# M708B.net
KiCad netlist of a schematic drawn in EAGLE
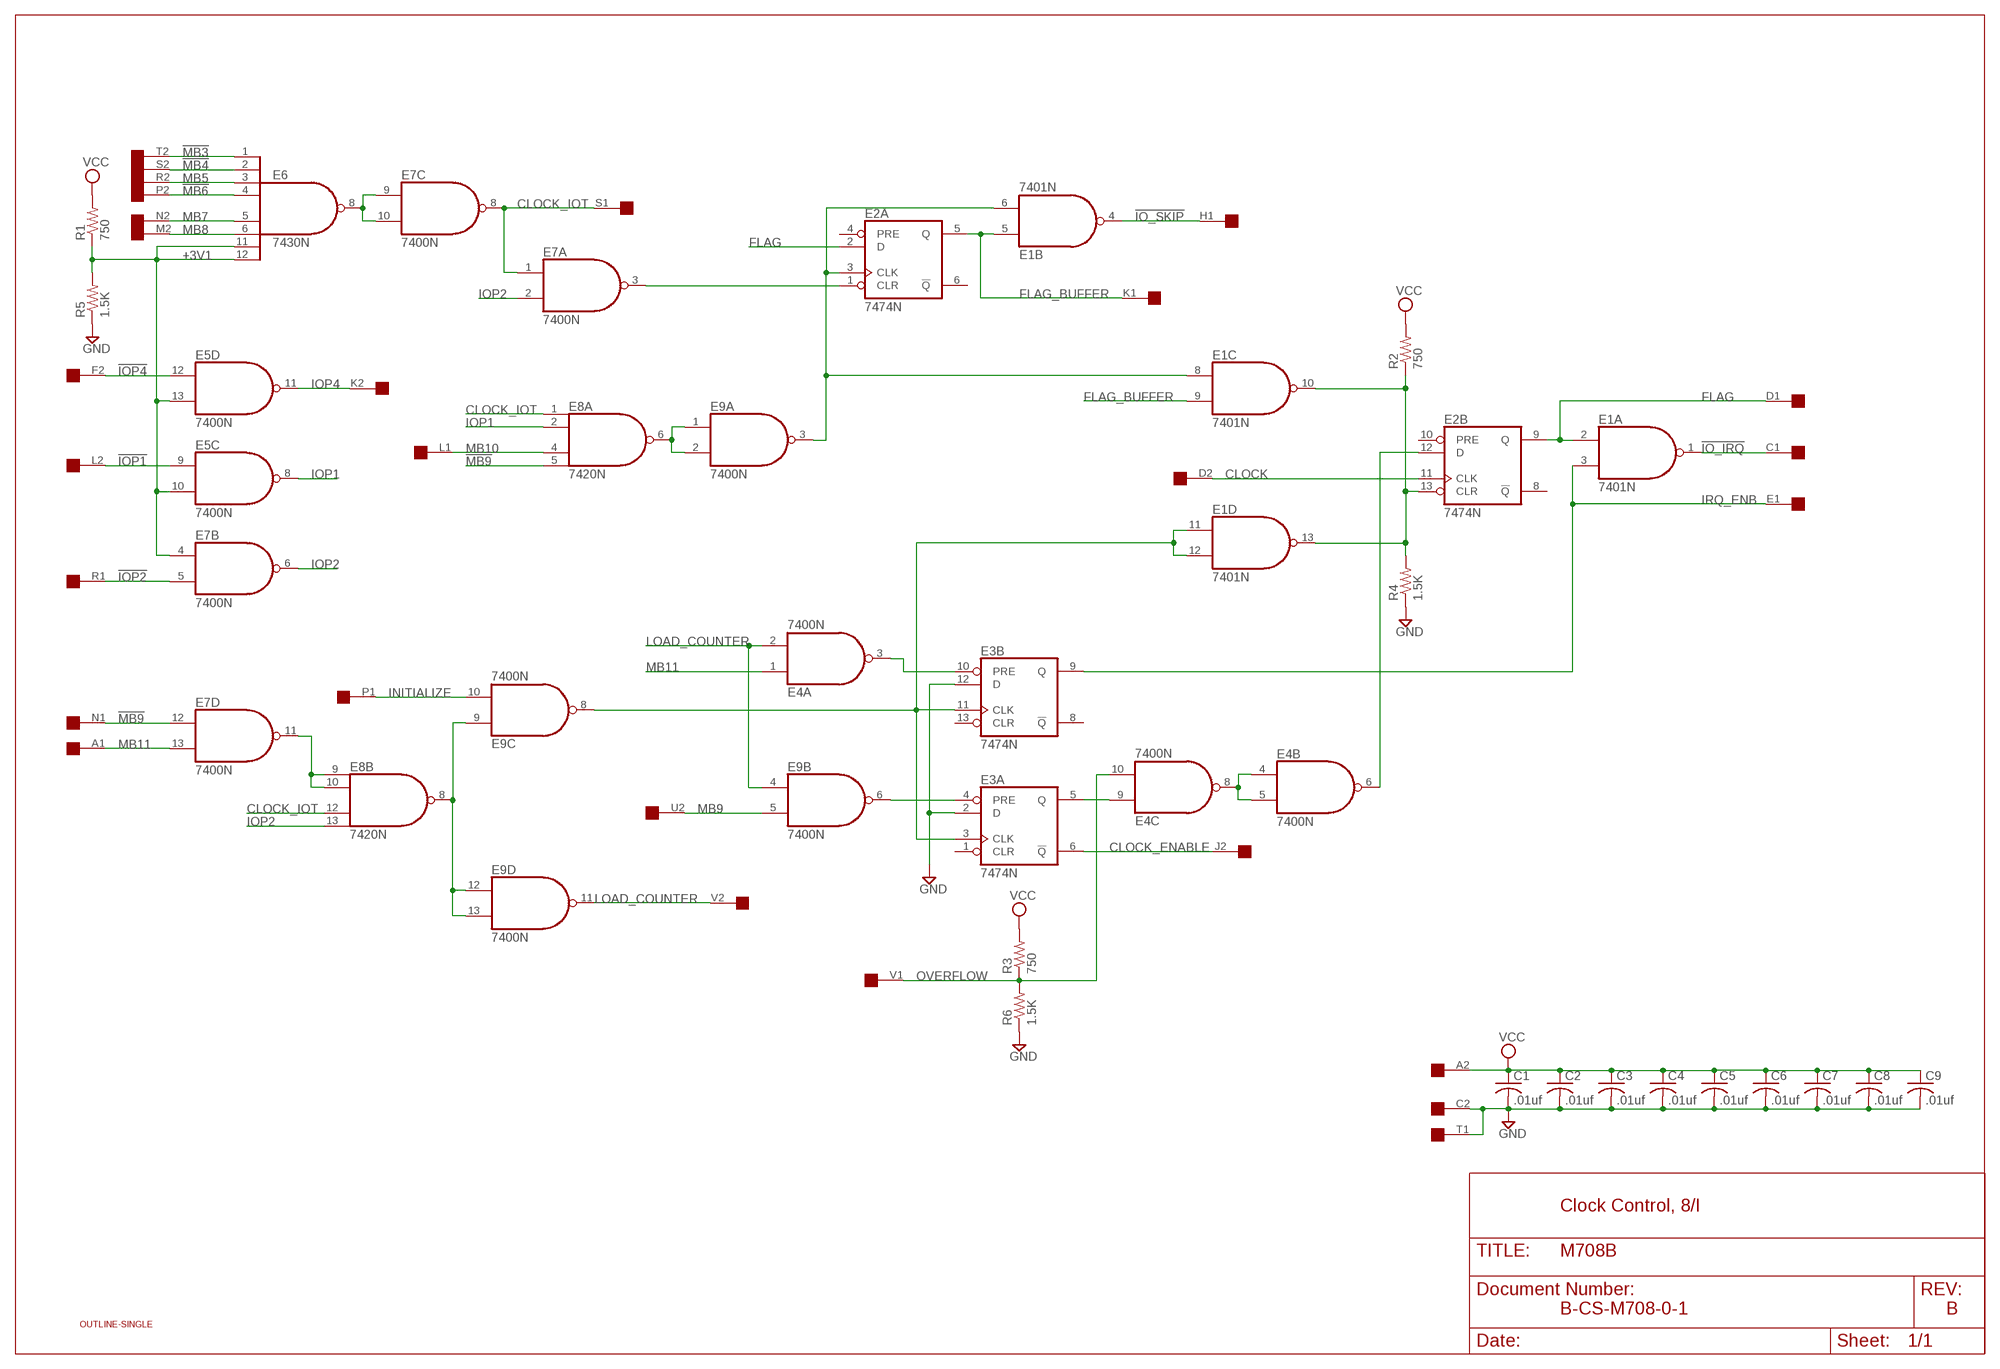
[diagram p0: schematic, sheet 1]

(export (version "E")
  (design (tool "Eeschema 10.0.6"))
  (components
    (comp (ref "C1")
      (value ".01uf")
      (footprint "eagle-import:C075-032X103")
      (libsource (lib "eagle-import") (part "C-US075-032X103"))
    )
    (comp (ref "C2")
      (value ".01uf")
      (footprint "eagle-import:C075-032X103")
      (libsource (lib "eagle-import") (part "C-US075-032X103"))
    )
    (comp (ref "C3")
      (value ".01uf")
      (footprint "eagle-import:C075-032X103")
      (libsource (lib "eagle-import") (part "C-US075-032X103"))
    )
    (comp (ref "C4")
      (value ".01uf")
      (footprint "eagle-import:C075-032X103")
      (libsource (lib "eagle-import") (part "C-US075-032X103"))
    )
    (comp (ref "C5")
      (value ".01uf")
      (footprint "eagle-import:C075-032X103")
      (libsource (lib "eagle-import") (part "C-US075-032X103"))
    )
    (comp (ref "C6")
      (value ".01uf")
      (footprint "eagle-import:C075-032X103")
      (libsource (lib "eagle-import") (part "C-US075-032X103"))
    )
    (comp (ref "C7")
      (value ".01uf")
      (footprint "eagle-import:C075-032X103")
      (libsource (lib "eagle-import") (part "C-US075-032X103"))
    )
    (comp (ref "C8")
      (value ".01uf")
      (footprint "eagle-import:C075-032X103")
      (libsource (lib "eagle-import") (part "C-US075-032X103"))
    )
    (comp (ref "C9")
      (value ".01uf")
      (footprint "eagle-import:C075-032X103")
      (libsource (lib "eagle-import") (part "C-US075-032X103"))
    )
    (comp (ref "E1")
      (value "7401N")
      (footprint "eagle-import:DIL14")
      (libsource (lib "eagle-import") (part "7401NLS"))
    )
    (comp (ref "E2")
      (value "7474N")
      (footprint "eagle-import:DIL14")
      (libsource (lib "eagle-import") (part "7474NS"))
    )
    (comp (ref "E3")
      (value "7474N")
      (footprint "eagle-import:DIL14")
      (libsource (lib "eagle-import") (part "7474NS"))
    )
    (comp (ref "E4")
      (value "7400N")
      (footprint "eagle-import:DIL14")
      (libsource (lib "eagle-import") (part "7400N"))
    )
    (comp (ref "E5")
      (value "7400N")
      (footprint "eagle-import:DIL14")
      (libsource (lib "eagle-import") (part "7400N"))
    )
    (comp (ref "E6")
      (value "7430N")
      (footprint "eagle-import:DIL14")
      (libsource (lib "eagle-import") (part "7430N"))
    )
    (comp (ref "E7")
      (value "7400N")
      (footprint "eagle-import:DIL14")
      (libsource (lib "eagle-import") (part "7400N"))
    )
    (comp (ref "E8")
      (value "7420N")
      (footprint "eagle-import:DIL14")
      (libsource (lib "eagle-import") (part "7420NS"))
    )
    (comp (ref "E9")
      (value "7400N")
      (footprint "eagle-import:DIL14")
      (libsource (lib "eagle-import") (part "7400N"))
    )
    (comp (ref "R1")
      (value "750")
      (footprint "eagle-import:0207_10")
      (libsource (lib "eagle-import") (part "R-US_0207/10"))
    )
    (comp (ref "R2")
      (value "750")
      (footprint "eagle-import:0207_10")
      (libsource (lib "eagle-import") (part "R-US_0207/10"))
    )
    (comp (ref "R3")
      (value "750")
      (footprint "eagle-import:0207_10")
      (libsource (lib "eagle-import") (part "R-US_0207/10"))
    )
    (comp (ref "R4")
      (value "1.5K")
      (footprint "eagle-import:0207_10")
      (libsource (lib "eagle-import") (part "R-US_0207/10"))
    )
    (comp (ref "R5")
      (value "1.5K")
      (footprint "eagle-import:0207_10")
      (libsource (lib "eagle-import") (part "R-US_0207/10"))
    )
    (comp (ref "R6")
      (value "1.5K")
      (footprint "eagle-import:0207_10")
      (libsource (lib "eagle-import") (part "R-US_0207/10"))
    )
    (comp (ref "U$1")
      (value "SINGLE")
      (footprint "eagle-import:EDGE-CON2")
      (libsource (lib "eagle-import") (part "SINGLE"))
    )
    (comp (ref "U$4")
      (value "OUTLINE-SINGLE")
      (footprint "eagle-import:SINGLE")
      (libsource (lib "eagle-import") (part "OUTLINE-SINGLE"))
    )
  )
  (nets
    (net (code "1") (name "/+3V1") (class "Default")
      (node (ref "E5") (pin "10") (pinfunction "I1_10") (pintype "input"))
      (node (ref "E5") (pin "13") (pinfunction "I1_13") (pintype "input"))
      (node (ref "E6") (pin "11") (pinfunction "I6_11") (pintype "input"))
      (node (ref "E6") (pin "12") (pinfunction "I7_12") (pintype "input"))
      (node (ref "E7") (pin "4") (pinfunction "I0_4") (pintype "input"))
      (node (ref "R1") (pin "1") (pinfunction "1_1") (pintype "passive"))
      (node (ref "R5") (pin "2") (pinfunction "2_2") (pintype "passive"))
    )
    (net (code "2") (name "/CLOCK") (class "Default")
      (node (ref "E2") (pin "11") (pinfunction "CLK_11") (pintype "input"))
      (node (ref "U$1") (pin "D2") (pinfunction "1_D2") (pintype "bidirectional"))
    )
    (net (code "3") (name "/CLOCK_ENABLE") (class "Default")
      (node (ref "E3") (pin "6") (pinfunction "~{Q}_6") (pintype "output"))
      (node (ref "U$1") (pin "J2") (pinfunction "1_J2") (pintype "bidirectional"))
    )
    (net (code "4") (name "/CLOCK_IOT") (class "Default")
      (node (ref "E7") (pin "1") (pinfunction "I0_1") (pintype "input"))
      (node (ref "E7") (pin "8") (pinfunction "O_8") (pintype "output"))
      (node (ref "E8") (pin "1") (pinfunction "I0_1") (pintype "input"))
      (node (ref "E8") (pin "12") (pinfunction "I2_12") (pintype "input"))
      (node (ref "U$1") (pin "S1") (pinfunction "1_S1") (pintype "bidirectional"))
    )
    (net (code "5") (name "/FLAG") (class "Default")
      (node (ref "E1") (pin "2") (pinfunction "I0_2") (pintype "input"))
      (node (ref "E2") (pin "2") (pinfunction "D_2") (pintype "input"))
      (node (ref "E2") (pin "9") (pinfunction "Q_9") (pintype "output"))
      (node (ref "U$1") (pin "D1") (pinfunction "1_D1") (pintype "bidirectional"))
    )
    (net (code "6") (name "/FLAG_BUFFER") (class "Default")
      (node (ref "E1") (pin "5") (pinfunction "I0_5") (pintype "input"))
      (node (ref "E1") (pin "9") (pinfunction "I1_9") (pintype "input"))
      (node (ref "E2") (pin "5") (pinfunction "Q_5") (pintype "output"))
      (node (ref "U$1") (pin "K1") (pinfunction "1_K1") (pintype "bidirectional"))
    )
    (net (code "7") (name "/INITIALIZE") (class "Default")
      (node (ref "E9") (pin "10") (pinfunction "I1_10") (pintype "input"))
      (node (ref "U$1") (pin "P1") (pinfunction "1_P1") (pintype "bidirectional"))
    )
    (net (code "8") (name "/IOP1") (class "Default")
      (node (ref "E5") (pin "8") (pinfunction "O_8") (pintype "output"))
      (node (ref "E8") (pin "2") (pinfunction "I1_2") (pintype "input"))
    )
    (net (code "9") (name "/IOP2") (class "Default")
      (node (ref "E7") (pin "2") (pinfunction "I1_2") (pintype "input"))
      (node (ref "E7") (pin "6") (pinfunction "O_6") (pintype "output"))
      (node (ref "E8") (pin "13") (pinfunction "I3_13") (pintype "input"))
    )
    (net (code "10") (name "/IOP4") (class "Default")
      (node (ref "E5") (pin "11") (pinfunction "O_11") (pintype "output"))
      (node (ref "U$1") (pin "K2") (pinfunction "1_K2") (pintype "bidirectional"))
    )
    (net (code "11") (name "/IRQ_ENB") (class "Default")
      (node (ref "E1") (pin "3") (pinfunction "I1_3") (pintype "input"))
      (node (ref "E3") (pin "9") (pinfunction "Q_9") (pintype "output"))
      (node (ref "U$1") (pin "E1") (pinfunction "1_E1") (pintype "bidirectional"))
    )
    (net (code "12") (name "/LOAD_COUNTER") (class "Default")
      (node (ref "E4") (pin "2") (pinfunction "I1_2") (pintype "input"))
      (node (ref "E9") (pin "11") (pinfunction "O_11") (pintype "output"))
      (node (ref "E9") (pin "4") (pinfunction "I0_4") (pintype "input"))
      (node (ref "U$1") (pin "V2") (pinfunction "1_V2") (pintype "bidirectional"))
    )
    (net (code "13") (name "/MB5") (class "Default")
      (node (ref "E6") (pin "3") (pinfunction "I2_3") (pintype "input"))
      (node (ref "U$1") (pin "R2") (pinfunction "1_R2") (pintype "bidirectional"))
    )
    (net (code "14") (name "/MB7") (class "Default")
      (node (ref "E6") (pin "5") (pinfunction "I4_5") (pintype "input"))
      (node (ref "U$1") (pin "N2") (pinfunction "1_N2") (pintype "bidirectional"))
    )
    (net (code "15") (name "/MB8") (class "Default")
      (node (ref "E6") (pin "6") (pinfunction "I5_6") (pintype "input"))
      (node (ref "U$1") (pin "M2") (pinfunction "1_M2") (pintype "bidirectional"))
    )
    (net (code "16") (name "/MB9") (class "Default")
      (node (ref "E9") (pin "5") (pinfunction "I1_5") (pintype "input"))
      (node (ref "U$1") (pin "U2") (pinfunction "1_U2") (pintype "bidirectional"))
    )
    (net (code "17") (name "/MB10") (class "Default")
      (node (ref "E8") (pin "4") (pinfunction "I2_4") (pintype "input"))
      (node (ref "U$1") (pin "L1") (pinfunction "1_L1") (pintype "bidirectional"))
    )
    (net (code "18") (name "/MB11") (class "Default")
      (node (ref "E4") (pin "1") (pinfunction "I0_1") (pintype "input"))
      (node (ref "E7") (pin "13") (pinfunction "I1_13") (pintype "input"))
      (node (ref "U$1") (pin "A1") (pinfunction "1_A1") (pintype "bidirectional"))
    )
    (net (code "19") (name "/OVERFLOW") (class "Default")
      (node (ref "E4") (pin "10") (pinfunction "I1_10") (pintype "input"))
      (node (ref "R3") (pin "1") (pinfunction "1_1") (pintype "passive"))
      (node (ref "R6") (pin "2") (pinfunction "2_2") (pintype "passive"))
      (node (ref "U$1") (pin "V1") (pinfunction "1_V1") (pintype "bidirectional"))
    )
    (net (code "20") (name "/~{IOP1}") (class "Default")
      (node (ref "E5") (pin "9") (pinfunction "I0_9") (pintype "input"))
      (node (ref "U$1") (pin "L2") (pinfunction "1_L2") (pintype "bidirectional"))
    )
    (net (code "21") (name "/~{IOP2}") (class "Default")
      (node (ref "E7") (pin "5") (pinfunction "I1_5") (pintype "input"))
      (node (ref "U$1") (pin "R1") (pinfunction "1_R1") (pintype "bidirectional"))
    )
    (net (code "22") (name "/~{IOP4}") (class "Default")
      (node (ref "E5") (pin "12") (pinfunction "I0_12") (pintype "input"))
      (node (ref "U$1") (pin "F2") (pinfunction "1_F2") (pintype "bidirectional"))
    )
    (net (code "23") (name "/~{IO_IRQ}") (class "Default")
      (node (ref "E1") (pin "1") (pinfunction "O_1") (pintype "open_collector"))
      (node (ref "U$1") (pin "C1") (pinfunction "1_C1") (pintype "bidirectional"))
    )
    (net (code "24") (name "/~{IO_SKIP}") (class "Default")
      (node (ref "E1") (pin "4") (pinfunction "O_4") (pintype "open_collector"))
      (node (ref "U$1") (pin "H1") (pinfunction "1_H1") (pintype "bidirectional"))
    )
    (net (code "25") (name "/~{MB3}") (class "Default")
      (node (ref "E6") (pin "1") (pinfunction "I0_1") (pintype "input"))
      (node (ref "U$1") (pin "T2") (pinfunction "1_T2") (pintype "bidirectional"))
    )
    (net (code "26") (name "/~{MB4}") (class "Default")
      (node (ref "E6") (pin "2") (pinfunction "I1_2") (pintype "input"))
      (node (ref "U$1") (pin "S2") (pinfunction "1_S2") (pintype "bidirectional"))
    )
    (net (code "27") (name "/~{MB6}") (class "Default")
      (node (ref "E6") (pin "4") (pinfunction "I3_4") (pintype "input"))
      (node (ref "U$1") (pin "P2") (pinfunction "1_P2") (pintype "bidirectional"))
    )
    (net (code "28") (name "/~{MB9}") (class "Default")
      (node (ref "E7") (pin "12") (pinfunction "I0_12") (pintype "input"))
      (node (ref "E8") (pin "5") (pinfunction "I3_5") (pintype "input"))
      (node (ref "U$1") (pin "N1") (pinfunction "1_N1") (pintype "bidirectional"))
    )
    (net (code "29") (name "GND") (class "Default")
      (node (ref "C1") (pin "2") (pinfunction "2_2") (pintype "passive"))
      (node (ref "C2") (pin "2") (pinfunction "2_2") (pintype "passive"))
      (node (ref "C3") (pin "2") (pinfunction "2_2") (pintype "passive"))
      (node (ref "C4") (pin "2") (pinfunction "2_2") (pintype "passive"))
      (node (ref "C5") (pin "2") (pinfunction "2_2") (pintype "passive"))
      (node (ref "C6") (pin "2") (pinfunction "2_2") (pintype "passive"))
      (node (ref "C7") (pin "2") (pinfunction "2_2") (pintype "passive"))
      (node (ref "C8") (pin "2") (pinfunction "2_2") (pintype "passive"))
      (node (ref "C9") (pin "2") (pinfunction "2_2") (pintype "passive"))
      (node (ref "E3") (pin "12") (pinfunction "D_12") (pintype "input"))
      (node (ref "E3") (pin "2") (pinfunction "D_2") (pintype "input"))
      (node (ref "R4") (pin "1") (pinfunction "1_1") (pintype "passive"))
      (node (ref "R5") (pin "1") (pinfunction "1_1") (pintype "passive"))
      (node (ref "R6") (pin "1") (pinfunction "1_1") (pintype "passive"))
      (node (ref "U$1") (pin "C2") (pinfunction "1_C2") (pintype "bidirectional"))
      (node (ref "U$1") (pin "T1") (pinfunction "1_T1") (pintype "bidirectional"))
    )
    (net (code "30") (name "Net-(E1B-I1)") (class "Default")
      (node (ref "E1") (pin "6") (pinfunction "I1_6") (pintype "input"))
      (node (ref "E1") (pin "8") (pinfunction "I0_8") (pintype "input"))
      (node (ref "E2") (pin "3") (pinfunction "CLK_3") (pintype "input"))
      (node (ref "E9") (pin "3") (pinfunction "O_3") (pintype "output"))
    )
    (net (code "31") (name "Net-(E1C-O)") (class "Default")
      (node (ref "E1") (pin "10") (pinfunction "O_10") (pintype "open_collector"))
      (node (ref "E1") (pin "13") (pinfunction "O_13") (pintype "open_collector"))
      (node (ref "E2") (pin "13") (pinfunction "CLR_13") (pintype "input"))
      (node (ref "R2") (pin "1") (pinfunction "1_1") (pintype "passive"))
      (node (ref "R4") (pin "2") (pinfunction "2_2") (pintype "passive"))
    )
    (net (code "32") (name "Net-(E1D-I0)") (class "Default")
      (node (ref "E1") (pin "11") (pinfunction "I0_11") (pintype "input"))
      (node (ref "E1") (pin "12") (pinfunction "I1_12") (pintype "input"))
      (node (ref "E3") (pin "11") (pinfunction "CLK_11") (pintype "input"))
      (node (ref "E3") (pin "3") (pinfunction "CLK_3") (pintype "input"))
      (node (ref "E9") (pin "8") (pinfunction "O_8") (pintype "output"))
    )
    (net (code "33") (name "Net-(E2A-CLR)") (class "Default")
      (node (ref "E2") (pin "1") (pinfunction "CLR_1") (pintype "input"))
      (node (ref "E7") (pin "3") (pinfunction "O_3") (pintype "output"))
    )
    (net (code "34") (name "Net-(E2B-D)") (class "Default")
      (node (ref "E2") (pin "12") (pinfunction "D_12") (pintype "input"))
      (node (ref "E4") (pin "6") (pinfunction "O_6") (pintype "output"))
    )
    (net (code "35") (name "Net-(E3A-PRE)") (class "Default")
      (node (ref "E3") (pin "4") (pinfunction "PRE_4") (pintype "input"))
      (node (ref "E9") (pin "6") (pinfunction "O_6") (pintype "output"))
    )
    (net (code "36") (name "Net-(E3A-Q)") (class "Default")
      (node (ref "E3") (pin "5") (pinfunction "Q_5") (pintype "output"))
      (node (ref "E4") (pin "9") (pinfunction "I0_9") (pintype "input"))
    )
    (net (code "37") (name "Net-(E3B-PRE)") (class "Default")
      (node (ref "E3") (pin "10") (pinfunction "PRE_10") (pintype "input"))
      (node (ref "E4") (pin "3") (pinfunction "O_3") (pintype "output"))
    )
    (net (code "38") (name "Net-(E4B-I0)") (class "Default")
      (node (ref "E4") (pin "4") (pinfunction "I0_4") (pintype "input"))
      (node (ref "E4") (pin "5") (pinfunction "I1_5") (pintype "input"))
      (node (ref "E4") (pin "8") (pinfunction "O_8") (pintype "output"))
    )
    (net (code "39") (name "Net-(E6A-O)") (class "Default")
      (node (ref "E6") (pin "8") (pinfunction "O_8") (pintype "output"))
      (node (ref "E7") (pin "10") (pinfunction "I1_10") (pintype "input"))
      (node (ref "E7") (pin "9") (pinfunction "I0_9") (pintype "input"))
    )
    (net (code "40") (name "Net-(E7D-O)") (class "Default")
      (node (ref "E7") (pin "11") (pinfunction "O_11") (pintype "output"))
      (node (ref "E8") (pin "10") (pinfunction "I1_10") (pintype "input"))
      (node (ref "E8") (pin "9") (pinfunction "I0_9") (pintype "input"))
    )
    (net (code "41") (name "Net-(E8A-O)") (class "Default")
      (node (ref "E8") (pin "6") (pinfunction "O_6") (pintype "output"))
      (node (ref "E9") (pin "1") (pinfunction "I0_1") (pintype "input"))
      (node (ref "E9") (pin "2") (pinfunction "I1_2") (pintype "input"))
    )
    (net (code "42") (name "Net-(E8B-O)") (class "Default")
      (node (ref "E8") (pin "8") (pinfunction "O_8") (pintype "output"))
      (node (ref "E9") (pin "12") (pinfunction "I0_12") (pintype "input"))
      (node (ref "E9") (pin "13") (pinfunction "I1_13") (pintype "input"))
      (node (ref "E9") (pin "9") (pinfunction "I0_9") (pintype "input"))
    )
    (net (code "43") (name "VCC") (class "Default")
      (node (ref "C1") (pin "1") (pinfunction "1_1") (pintype "passive"))
      (node (ref "C2") (pin "1") (pinfunction "1_1") (pintype "passive"))
      (node (ref "C3") (pin "1") (pinfunction "1_1") (pintype "passive"))
      (node (ref "C4") (pin "1") (pinfunction "1_1") (pintype "passive"))
      (node (ref "C5") (pin "1") (pinfunction "1_1") (pintype "passive"))
      (node (ref "C6") (pin "1") (pinfunction "1_1") (pintype "passive"))
      (node (ref "C7") (pin "1") (pinfunction "1_1") (pintype "passive"))
      (node (ref "C8") (pin "1") (pinfunction "1_1") (pintype "passive"))
      (node (ref "C9") (pin "1") (pinfunction "1_1") (pintype "passive"))
      (node (ref "R1") (pin "2") (pinfunction "2_2") (pintype "passive"))
      (node (ref "R2") (pin "2") (pinfunction "2_2") (pintype "passive"))
      (node (ref "R3") (pin "2") (pinfunction "2_2") (pintype "passive"))
      (node (ref "U$1") (pin "A2") (pinfunction "1_A2") (pintype "bidirectional"))
    )
    (net (code "44") (name "unconnected-(E2A-PRE-Pad4)") (class "Default")
      (node (ref "E2") (pin "4") (pinfunction "PRE_4") (pintype "input"))
    )
    (net (code "45") (name "unconnected-(E2A-~{Q}-Pad6)") (class "Default")
      (node (ref "E2") (pin "6") (pinfunction "~{Q}_6") (pintype "output"))
    )
    (net (code "46") (name "unconnected-(E2B-PRE-Pad10)") (class "Default")
      (node (ref "E2") (pin "10") (pinfunction "PRE_10") (pintype "input"))
    )
    (net (code "47") (name "unconnected-(E2B-~{Q}-Pad8)") (class "Default")
      (node (ref "E2") (pin "8") (pinfunction "~{Q}_8") (pintype "output"))
    )
    (net (code "48") (name "unconnected-(E3A-CLR-Pad1)") (class "Default")
      (node (ref "E3") (pin "1") (pinfunction "CLR_1") (pintype "input"))
    )
    (net (code "49") (name "unconnected-(E3B-CLR-Pad13)") (class "Default")
      (node (ref "E3") (pin "13") (pinfunction "CLR_13") (pintype "input"))
    )
    (net (code "50") (name "unconnected-(E3B-~{Q}-Pad8)") (class "Default")
      (node (ref "E3") (pin "8") (pinfunction "~{Q}_8") (pintype "output"))
    )
  )
)
